# FPGA_Banks.net
KiCad netlist of a schematic drawn in Altium Designer
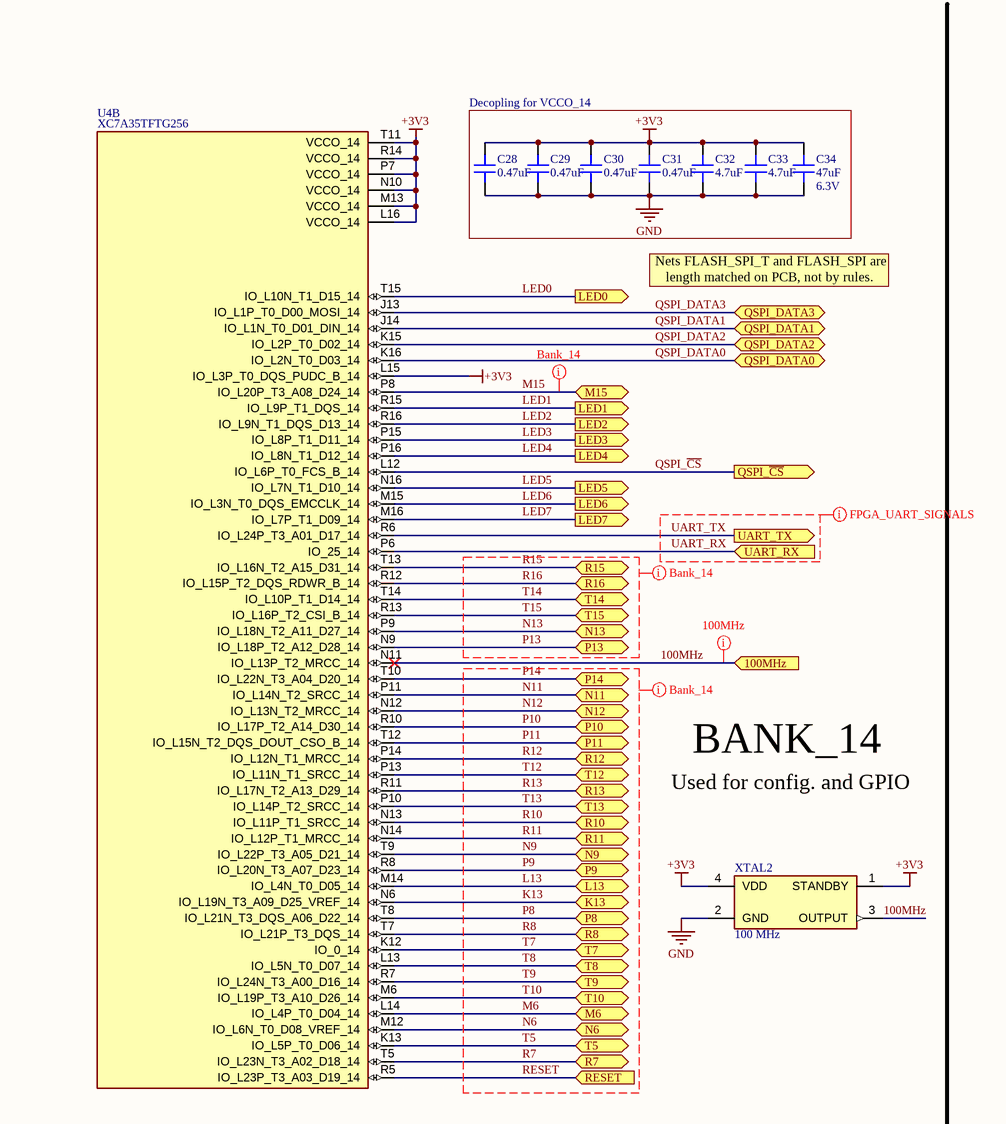
[diagram p0: FPGA_Banks.SchDoc, top left]
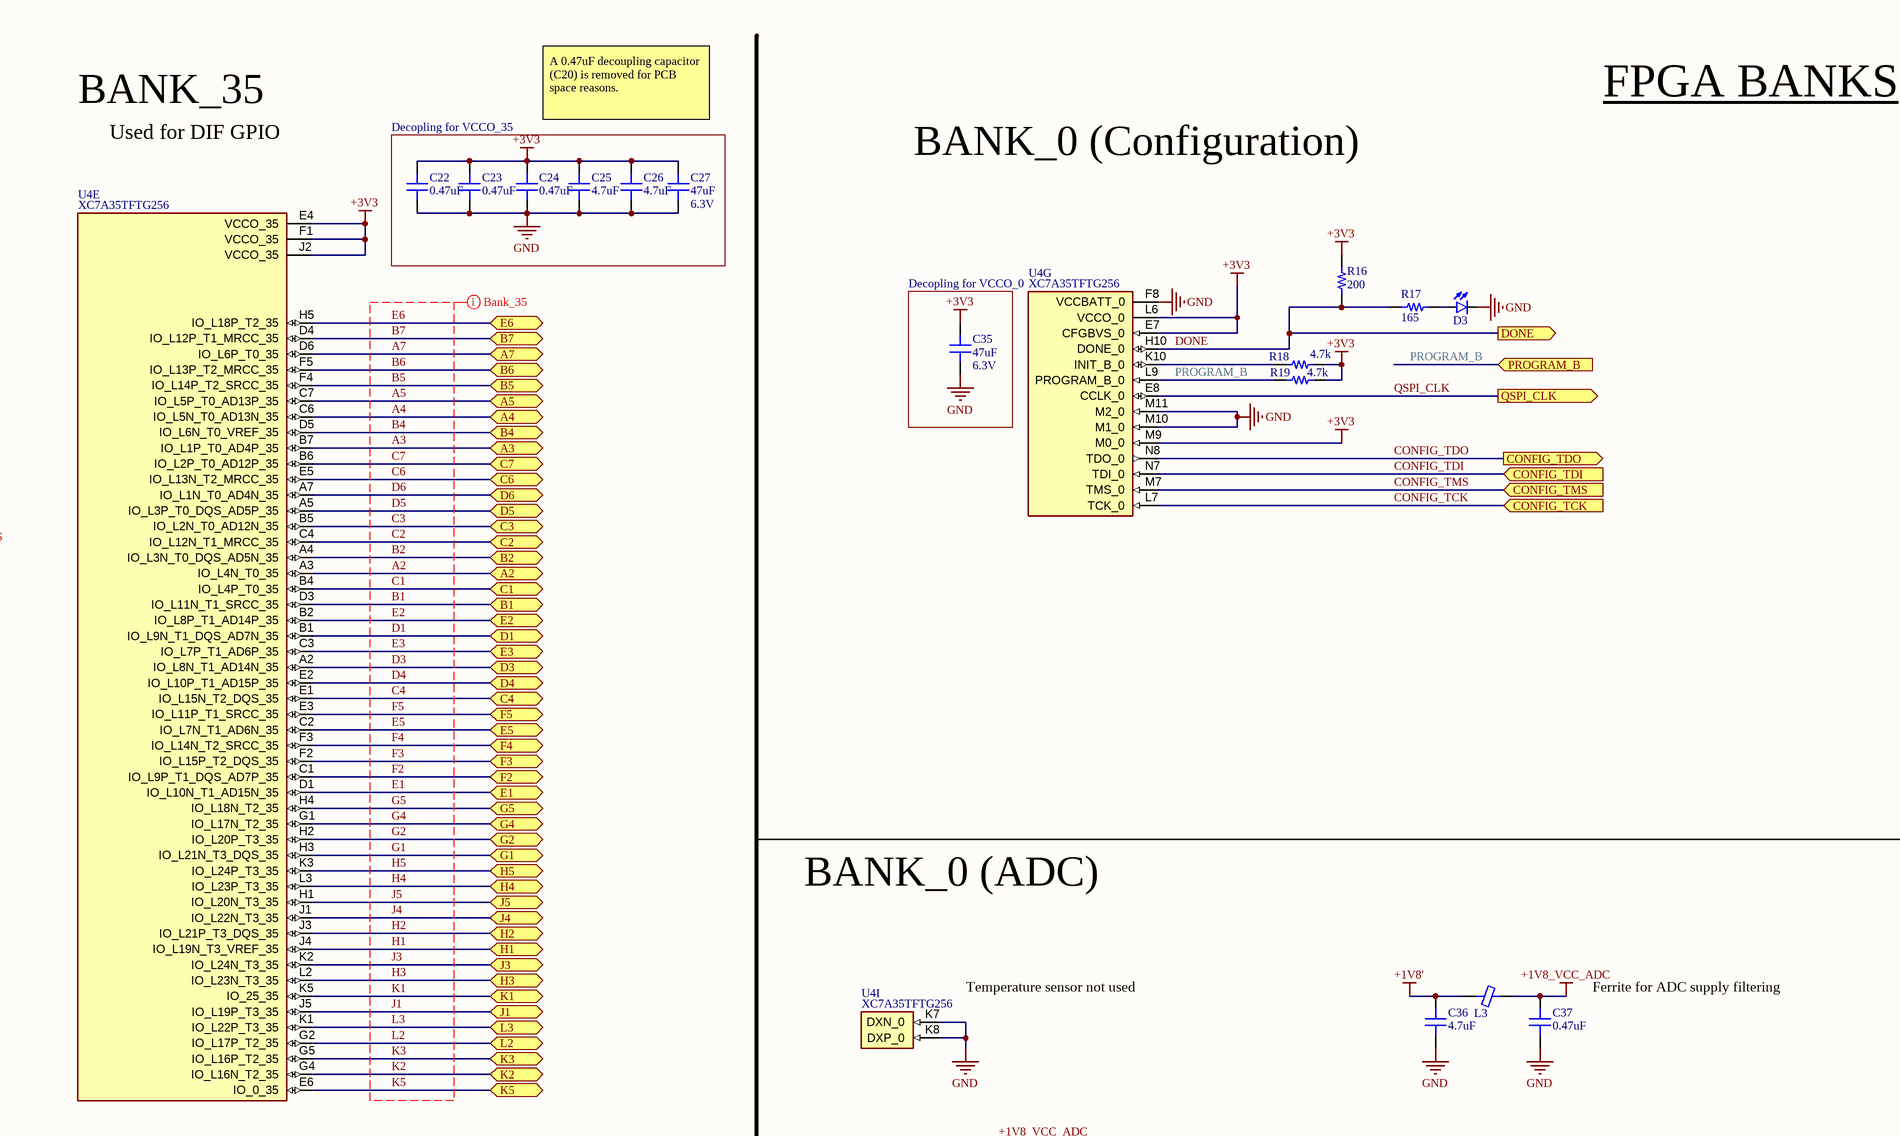
[diagram p1: FPGA_Banks.SchDoc, top right]
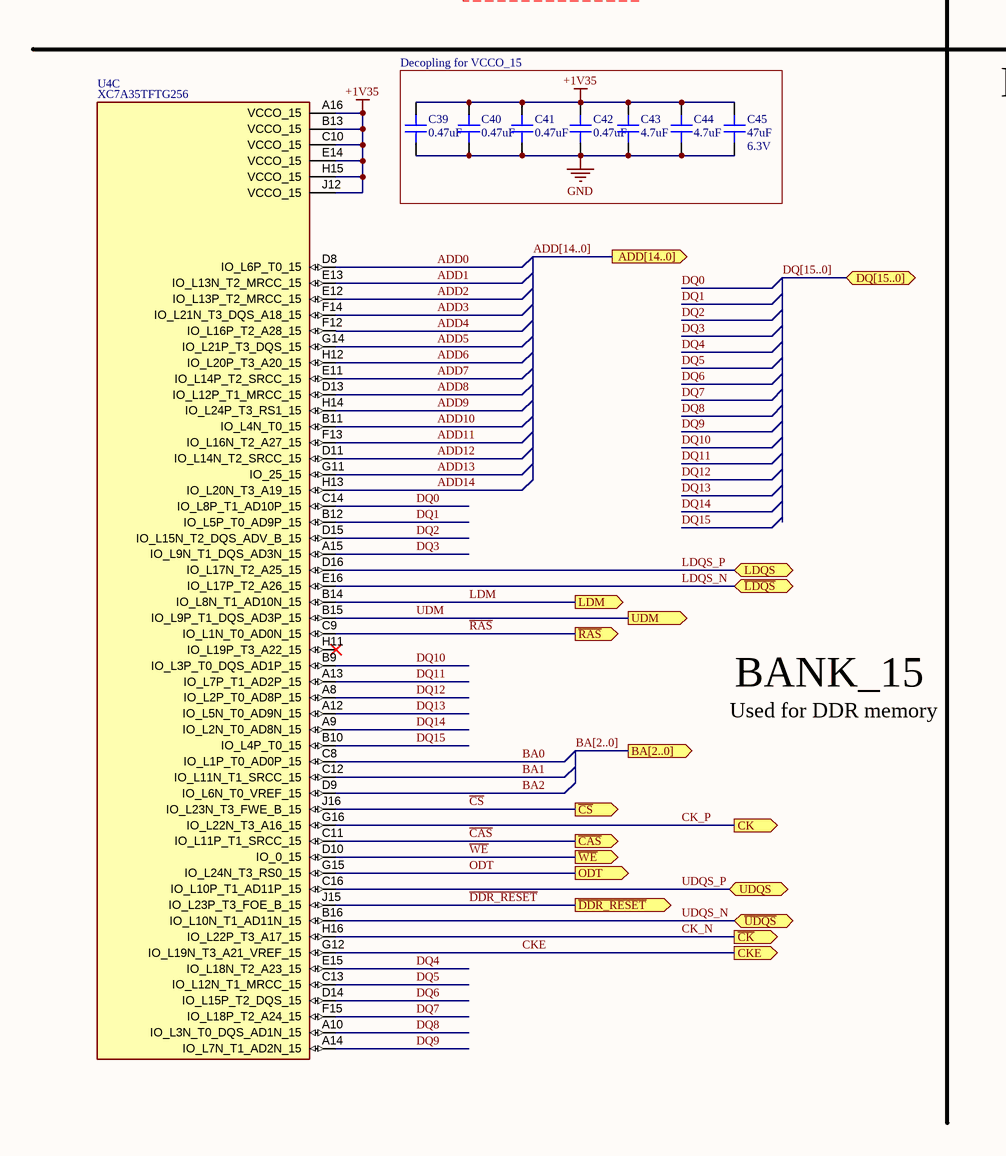
[diagram p2: FPGA_Banks.SchDoc, bottom left]
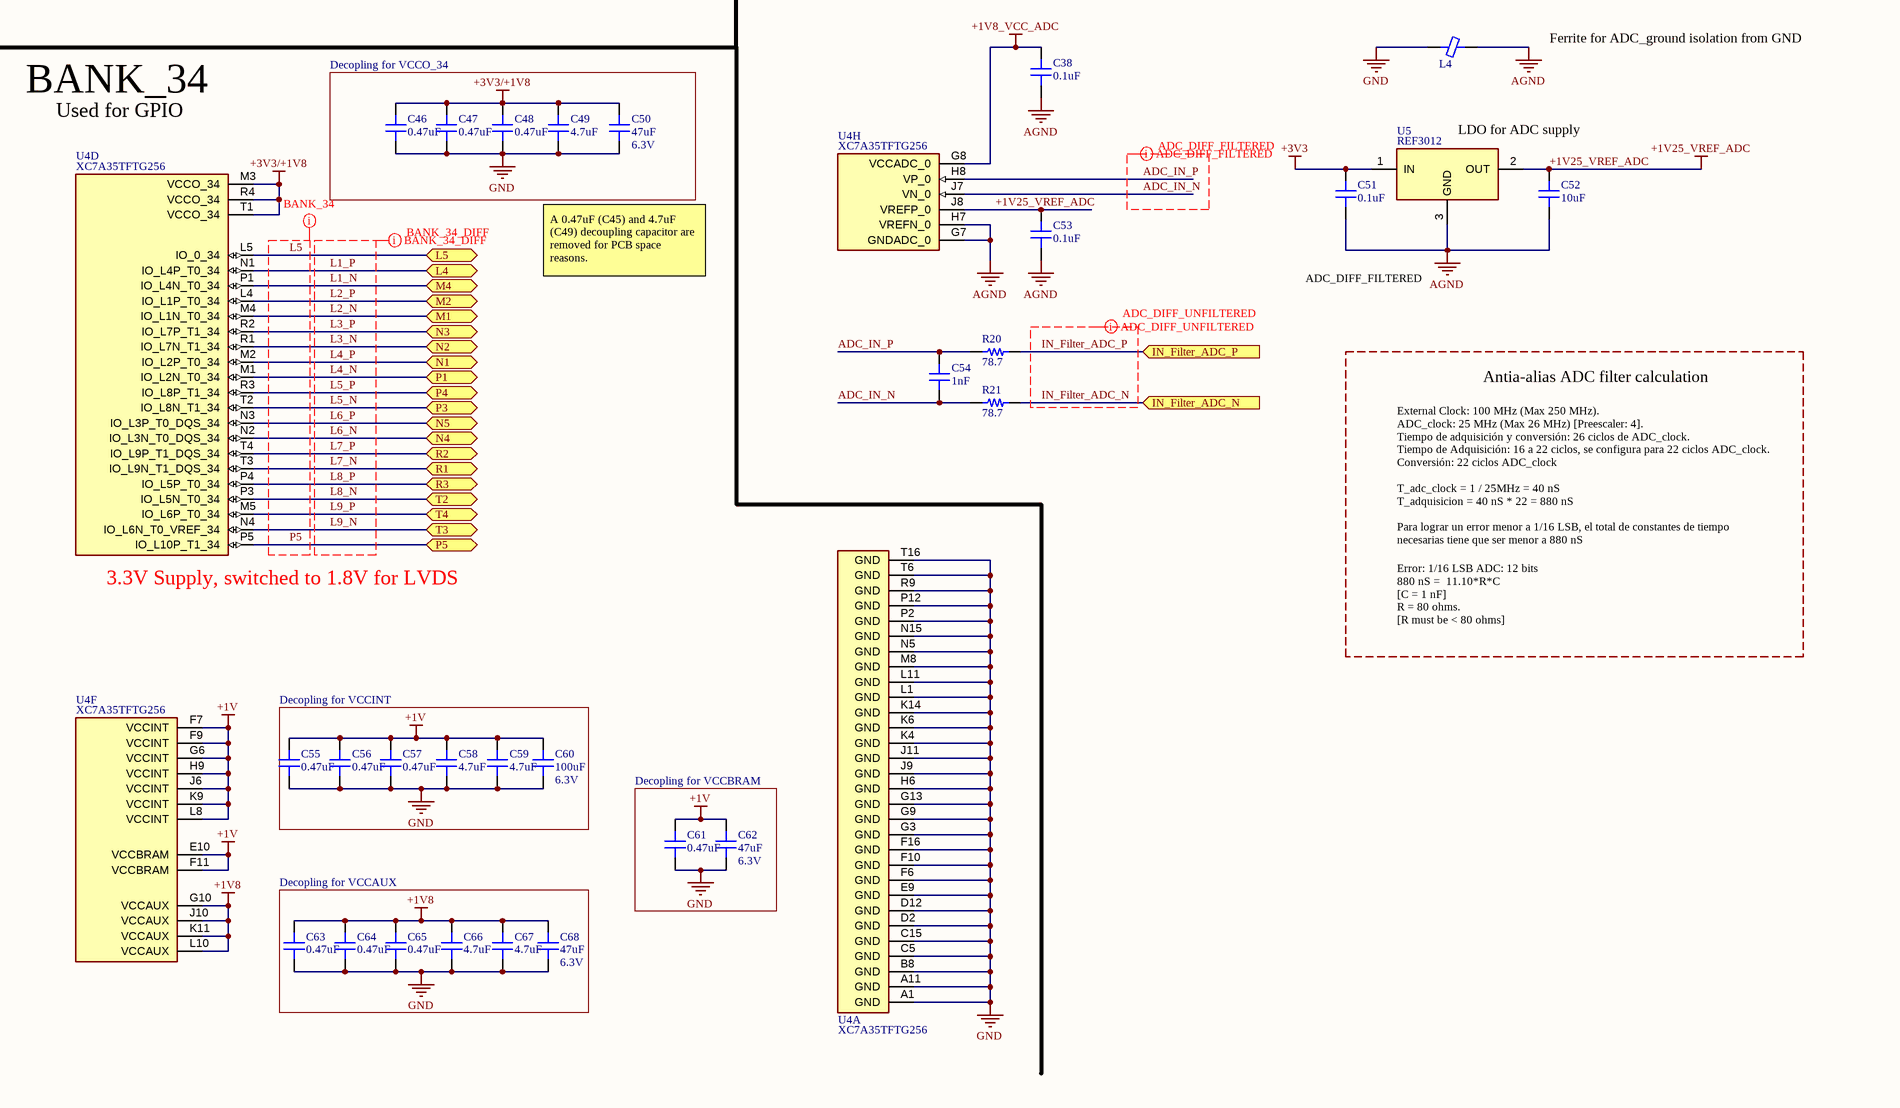
[diagram p3: FPGA_Banks.SchDoc, bottom right]

(export (version "E")
  (design (tool "Eeschema 10.0.6"))
  (components
    (comp (ref "C22")
      (value "0.47uF")
      (footprint "CAP0402")
      (description "CAP CER 0.47uF 10V X7R 0402 10%")
      (fields (field (name "PARTNUMBER") "C0603C474K4RAC") (field (name "TOLERANCE") "10%"))
      (libsource (lib "Pasivos") (part "C0402C474K8RAC"))
    )
    (comp (ref "C23")
      (value "0.47uF")
      (footprint "CAP0402")
      (description "CAP CER 0.47uF 10V X7R 0402 10%")
      (fields (field (name "PARTNUMBER") "C0603C474K4RAC") (field (name "TOLERANCE") "10%"))
      (libsource (lib "Pasivos") (part "C0402C474K8RAC"))
    )
    (comp (ref "C24")
      (value "0.47uF")
      (footprint "CAP0402")
      (description "CAP CER 0.47uF 10V X7R 0402 10%")
      (fields (field (name "PARTNUMBER") "C0603C474K4RAC") (field (name "TOLERANCE") "10%"))
      (libsource (lib "Pasivos") (part "C0402C474K8RAC"))
    )
    (comp (ref "C25")
      (value "4.7uF")
      (footprint "CAP0402")
      (description "CAP CER 4.7uF 6.3V X5R 0402 10%")
      (fields (field (name "PARTNUMBER") "C0402C475M9PAC") (field (name "TOLERANCE") "10%"))
      (libsource (lib "Pasivos") (part "C0402C475M9PAC"))
    )
    (comp (ref "C26")
      (value "4.7uF")
      (footprint "CAP0402")
      (description "CAP CER 4.7uF 6.3V X5R 0402 10%")
      (fields (field (name "PARTNUMBER") "C0402C475M9PAC") (field (name "TOLERANCE") "10%"))
      (libsource (lib "Pasivos") (part "C0402C475M9PAC"))
    )
    (comp (ref "C27")
      (value "47uF")
      (footprint "CAP0805")
      (description "CAP CER 47uF 6.3V X5R 0805 20%")
      (fields
        (field (name "VOLTAGE") "6.3V")
        (field (name "MANUFACTURER") "Samsung")
        (field (name "TOLERANCE") "20%")
      )
      (libsource (lib "Pasivos") (part "CL21A476MQYNNNE"))
    )
    (comp (ref "C28")
      (value "0.47uF")
      (footprint "CAP0402")
      (description "CAP CER 0.47uF 10V X7R 0402 10%")
      (fields (field (name "PARTNUMBER") "C0603C474K4RAC") (field (name "TOLERANCE") "10%"))
      (libsource (lib "Pasivos") (part "C0402C474K8RAC"))
    )
    (comp (ref "C29")
      (value "0.47uF")
      (footprint "CAP0402")
      (description "CAP CER 0.47uF 10V X7R 0402 10%")
      (fields (field (name "PARTNUMBER") "C0603C474K4RAC") (field (name "TOLERANCE") "10%"))
      (libsource (lib "Pasivos") (part "C0402C474K8RAC"))
    )
    (comp (ref "C30")
      (value "0.47uF")
      (footprint "CAP0402")
      (description "CAP CER 0.47uF 10V X7R 0402 10%")
      (fields (field (name "PARTNUMBER") "C0603C474K4RAC") (field (name "TOLERANCE") "10%"))
      (libsource (lib "Pasivos") (part "C0402C474K8RAC"))
    )
    (comp (ref "C31")
      (value "0.47uF")
      (footprint "CAP0402")
      (description "CAP CER 0.47uF 10V X7R 0402 10%")
      (fields (field (name "PARTNUMBER") "C0603C474K4RAC") (field (name "TOLERANCE") "10%"))
      (libsource (lib "Pasivos") (part "C0402C474K8RAC"))
    )
    (comp (ref "C32")
      (value "4.7uF")
      (footprint "CAP0402")
      (description "CAP CER 4.7uF 6.3V X5R 0402 10%")
      (fields (field (name "PARTNUMBER") "C0402C475M9PAC") (field (name "TOLERANCE") "10%"))
      (libsource (lib "Pasivos") (part "C0402C475M9PAC"))
    )
    (comp (ref "C33")
      (value "4.7uF")
      (footprint "CAP0402")
      (description "CAP CER 4.7uF 6.3V X5R 0402 10%")
      (fields (field (name "PARTNUMBER") "C0402C475M9PAC") (field (name "TOLERANCE") "10%"))
      (libsource (lib "Pasivos") (part "C0402C475M9PAC"))
    )
    (comp (ref "C34")
      (value "47uF")
      (footprint "CAP0805")
      (description "CAP CER 47uF 6.3V X5R 0805 20%")
      (fields
        (field (name "VOLTAGE") "6.3V")
        (field (name "MANUFACTURER") "Samsung")
        (field (name "TOLERANCE") "20%")
      )
      (libsource (lib "Pasivos") (part "CL21A476MQYNNNE"))
    )
    (comp (ref "C35")
      (value "47uF")
      (footprint "CAP0805")
      (description "CAP CER 47uF 6.3V X5R 0805 20%")
      (fields
        (field (name "MANUFACTURER") "Samsung")
        (field (name "VOLTAGE") "6.3V")
        (field (name "TOLERANCE") "20%")
      )
      (libsource (lib "Pasivos") (part "CL21A476MQYNNNE"))
    )
    (comp (ref "C36")
      (value "4.7uF")
      (footprint "CAP0402")
      (description "CAP CER 4.7uF 6.3V X5R 0402 10%")
      (fields (field (name "PARTNUMBER") "C0402C475M9PAC") (field (name "TOLERANCE") "10%"))
      (libsource (lib "Pasivos") (part "C0402C475M9PAC"))
    )
    (comp (ref "C37")
      (value "0.47uF")
      (footprint "CAP0402")
      (description "CAP CER 0.47uF 10V X7R 0402 10%")
      (fields (field (name "PARTNUMBER") "C0603C474K4RAC") (field (name "TOLERANCE") "10%"))
      (libsource (lib "Pasivos") (part "C0402C474K8RAC"))
    )
    (comp (ref "C38")
      (value "0.1uF")
      (footprint "CAP0402")
      (description "CAP CER 0.1uF 16V X7R 0402 10%")
      (fields (field (name "TOLERANCE") "10%") (field (name "VOLTAGE") "16V"))
      (libsource (lib "Pasivos") (part "C0402C104K4RAC"))
    )
    (comp (ref "C39")
      (value "0.47uF")
      (footprint "CAP0402")
      (description "CAP CER 0.47uF 10V X7R 0402 10%")
      (fields (field (name "PARTNUMBER") "C0603C474K4RAC") (field (name "TOLERANCE") "10%"))
      (libsource (lib "Pasivos") (part "C0402C474K8RAC"))
    )
    (comp (ref "C40")
      (value "0.47uF")
      (footprint "CAP0402")
      (description "CAP CER 0.47uF 10V X7R 0402 10%")
      (fields (field (name "PARTNUMBER") "C0603C474K4RAC") (field (name "TOLERANCE") "10%"))
      (libsource (lib "Pasivos") (part "C0402C474K8RAC"))
    )
    (comp (ref "C41")
      (value "0.47uF")
      (footprint "CAP0402")
      (description "CAP CER 0.47uF 10V X7R 0402 10%")
      (fields (field (name "PARTNUMBER") "C0603C474K4RAC") (field (name "TOLERANCE") "10%"))
      (libsource (lib "Pasivos") (part "C0402C474K8RAC"))
    )
    (comp (ref "C42")
      (value "0.47uF")
      (footprint "CAP0402")
      (description "CAP CER 0.47uF 10V X7R 0402 10%")
      (fields (field (name "PARTNUMBER") "C0603C474K4RAC") (field (name "TOLERANCE") "10%"))
      (libsource (lib "Pasivos") (part "C0402C474K8RAC"))
    )
    (comp (ref "C43")
      (value "4.7uF")
      (footprint "CAP0402")
      (description "CAP CER 4.7uF 6.3V X5R 0402 10%")
      (fields (field (name "PARTNUMBER") "C0402C475M9PAC") (field (name "TOLERANCE") "10%"))
      (libsource (lib "Pasivos") (part "C0402C475M9PAC"))
    )
    (comp (ref "C44")
      (value "4.7uF")
      (footprint "CAP0402")
      (description "CAP CER 4.7uF 6.3V X5R 0402 10%")
      (fields (field (name "PARTNUMBER") "C0402C475M9PAC") (field (name "TOLERANCE") "10%"))
      (libsource (lib "Pasivos") (part "C0402C475M9PAC"))
    )
    (comp (ref "C45")
      (value "47uF")
      (footprint "CAP0805")
      (description "CAP CER 47uF 6.3V X5R 0805 20%")
      (fields
        (field (name "VOLTAGE") "6.3V")
        (field (name "MANUFACTURER") "Samsung")
        (field (name "TOLERANCE") "20%")
      )
      (libsource (lib "Pasivos") (part "CL21A476MQYNNNE"))
    )
    (comp (ref "C46")
      (value "0.47uF")
      (footprint "CAP0402")
      (description "CAP CER 0.47uF 10V X7R 0402 10%")
      (fields (field (name "PARTNUMBER") "C0603C474K4RAC") (field (name "TOLERANCE") "10%"))
      (libsource (lib "Pasivos") (part "C0402C474K8RAC"))
    )
    (comp (ref "C47")
      (value "0.47uF")
      (footprint "CAP0402")
      (description "CAP CER 0.47uF 10V X7R 0402 10%")
      (fields (field (name "PARTNUMBER") "C0603C474K4RAC") (field (name "TOLERANCE") "10%"))
      (libsource (lib "Pasivos") (part "C0402C474K8RAC"))
    )
    (comp (ref "C48")
      (value "0.47uF")
      (footprint "CAP0402")
      (description "CAP CER 0.47uF 10V X7R 0402 10%")
      (fields (field (name "PARTNUMBER") "C0603C474K4RAC") (field (name "TOLERANCE") "10%"))
      (libsource (lib "Pasivos") (part "C0402C474K8RAC"))
    )
    (comp (ref "C49")
      (value "4.7uF")
      (footprint "CAP0402")
      (description "CAP CER 4.7uF 6.3V X5R 0402 10%")
      (fields (field (name "PARTNUMBER") "C0402C475M9PAC") (field (name "TOLERANCE") "10%"))
      (libsource (lib "Pasivos") (part "C0402C475M9PAC"))
    )
    (comp (ref "C50")
      (value "47uF")
      (footprint "CAP0805")
      (description "CAP CER 47uF 6.3V X5R 0805 20%")
      (fields
        (field (name "VOLTAGE") "6.3V")
        (field (name "MANUFACTURER") "Samsung")
        (field (name "TOLERANCE") "20%")
      )
      (libsource (lib "Pasivos") (part "CL21A476MQYNNNE"))
    )
    (comp (ref "C51")
      (value "0.1uF")
      (footprint "CAP0402")
      (description "CAP CER 0.1uF 16V X7R 0402 10%")
      (fields (field (name "TOLERANCE") "10%") (field (name "VOLTAGE") "16V"))
      (libsource (lib "Pasivos") (part "C0402C104K4RAC"))
    )
    (comp (ref "C52")
      (value "10uF")
      (footprint "CAP0402")
      (description "CAP CER 10uF 6.3V X5R 0402 10%")
      (fields (field (name "TOLERANCE") "10%") (field (name "MANUFACTURER") "Kemet"))
      (libsource (lib "Pasivos") (part "C0402C106M9PAC"))
    )
    (comp (ref "C53")
      (value "0.1uF")
      (footprint "CAP0402")
      (description "CAP CER 0.1uF 16V X7R 0402 10%")
      (fields (field (name "TOLERANCE") "10%") (field (name "VOLTAGE") "16V"))
      (libsource (lib "Pasivos") (part "C0402C104K4RAC"))
    )
    (comp (ref "C54")
      (value "1nF")
      (footprint "CAP0402")
      (description "CAP CER 1nF 16V X7R 0402 10%")
      (fields (field (name "TOLERANCE") "10%") (field (name "PARTNUMBER") "C0402C102K4RAC"))
      (libsource (lib "Pasivos") (part "C0402C102K4RAC"))
    )
    (comp (ref "C55")
      (value "0.47uF")
      (footprint "CAP0402")
      (description "CAP CER 0.47uF 10V X7R 0402 10%")
      (fields (field (name "PARTNUMBER") "C0603C474K4RAC") (field (name "TOLERANCE") "10%"))
      (libsource (lib "Pasivos") (part "C0402C474K8RAC"))
    )
    (comp (ref "C56")
      (value "0.47uF")
      (footprint "CAP0402")
      (description "CAP CER 0.47uF 10V X7R 0402 10%")
      (fields (field (name "PARTNUMBER") "C0603C474K4RAC") (field (name "TOLERANCE") "10%"))
      (libsource (lib "Pasivos") (part "C0402C474K8RAC"))
    )
    (comp (ref "C57")
      (value "0.47uF")
      (footprint "CAP0402")
      (description "CAP CER 0.47uF 10V X7R 0402 10%")
      (fields (field (name "PARTNUMBER") "C0603C474K4RAC") (field (name "TOLERANCE") "10%"))
      (libsource (lib "Pasivos") (part "C0402C474K8RAC"))
    )
    (comp (ref "C58")
      (value "4.7uF")
      (footprint "CAP0402")
      (description "CAP CER 4.7uF 6.3V X5R 0402 10%")
      (fields (field (name "PARTNUMBER") "C0402C475M9PAC") (field (name "TOLERANCE") "10%"))
      (libsource (lib "Pasivos") (part "C0402C475M9PAC"))
    )
    (comp (ref "C59")
      (value "4.7uF")
      (footprint "CAP0402")
      (description "CAP CER 4.7uF 6.3V X5R 0402 10%")
      (fields (field (name "PARTNUMBER") "C0402C475M9PAC") (field (name "TOLERANCE") "10%"))
      (libsource (lib "Pasivos") (part "C0402C475M9PAC"))
    )
    (comp (ref "C60")
      (value "100uF")
      (footprint "CAP1206")
      (description "CAP CER 100uF 6.3V X5R 1206 20%")
      (fields
        (field (name "PARTNUMBER") "C1206C107M9PAC")
        (field (name "TOLERANCE") "20%")
        (field (name "VOLTAGE") "6.3V")
      )
      (libsource (lib "Pasivos") (part "C1206C107M9PAC"))
    )
    (comp (ref "C61")
      (value "0.47uF")
      (footprint "CAP0402")
      (description "CAP CER 0.47uF 10V X7R 0402 10%")
      (fields (field (name "PARTNUMBER") "C0603C474K4RAC") (field (name "TOLERANCE") "10%"))
      (libsource (lib "Pasivos") (part "C0402C474K8RAC"))
    )
    (comp (ref "C62")
      (value "47uF")
      (footprint "CAP0805")
      (description "CAP CER 47uF 6.3V X5R 0805 20%")
      (fields
        (field (name "VOLTAGE") "6.3V")
        (field (name "MANUFACTURER") "Samsung")
        (field (name "TOLERANCE") "20%")
      )
      (libsource (lib "Pasivos") (part "CL21A476MQYNNNE"))
    )
    (comp (ref "C63")
      (value "0.47uF")
      (footprint "CAP0402")
      (description "CAP CER 0.47uF 10V X7R 0402 10%")
      (fields (field (name "PARTNUMBER") "C0603C474K4RAC") (field (name "TOLERANCE") "10%"))
      (libsource (lib "Pasivos") (part "C0402C474K8RAC"))
    )
    (comp (ref "C64")
      (value "0.47uF")
      (footprint "CAP0402")
      (description "CAP CER 0.47uF 10V X7R 0402 10%")
      (fields (field (name "PARTNUMBER") "C0603C474K4RAC") (field (name "TOLERANCE") "10%"))
      (libsource (lib "Pasivos") (part "C0402C474K8RAC"))
    )
    (comp (ref "C65")
      (value "0.47uF")
      (footprint "CAP0402")
      (description "CAP CER 0.47uF 10V X7R 0402 10%")
      (fields (field (name "PARTNUMBER") "C0603C474K4RAC") (field (name "TOLERANCE") "10%"))
      (libsource (lib "Pasivos") (part "C0402C474K8RAC"))
    )
    (comp (ref "C66")
      (value "4.7uF")
      (footprint "CAP0402")
      (description "CAP CER 4.7uF 6.3V X5R 0402 10%")
      (fields (field (name "PARTNUMBER") "C0402C475M9PAC") (field (name "TOLERANCE") "10%"))
      (libsource (lib "Pasivos") (part "C0402C475M9PAC"))
    )
    (comp (ref "C67")
      (value "4.7uF")
      (footprint "CAP0402")
      (description "CAP CER 4.7uF 6.3V X5R 0402 10%")
      (fields (field (name "PARTNUMBER") "C0402C475M9PAC") (field (name "TOLERANCE") "10%"))
      (libsource (lib "Pasivos") (part "C0402C475M9PAC"))
    )
    (comp (ref "C68")
      (value "47uF")
      (footprint "CAP0805")
      (description "CAP CER 47uF 6.3V X5R 0805 20%")
      (fields
        (field (name "VOLTAGE") "6.3V")
        (field (name "MANUFACTURER") "Samsung")
        (field (name "TOLERANCE") "20%")
      )
      (libsource (lib "Pasivos") (part "CL21A476MQYNNNE"))
    )
    (comp (ref "D3")
      (value "597-3305-607F")
      (footprint "0603_LED")
      (description "LED blue diffused 0603 SMD")
      (fields (field (name "MANUFACTURER") "Würth Elektronik") (field (name "PARTNUMBER") "150060BS55040"))
      (libsource (lib "Integrated_Circuits") (part "LED_BLUE_0603"))
    )
    (comp (ref "L3")
      (value "HZ0603C651R-10")
      (footprint "Fer0603")
      (description "FERRITE BEAD, 650 OHM, 0603, 1LN, 0603")
      (fields (field (name "MANUFACTURER") "Laird-Signal Integrity Products"))
      (libsource (lib "Pasivos") (part "HZ0603C651R-10"))
    )
    (comp (ref "L4")
      (value "HZ0603C651R-10")
      (footprint "Fer0603")
      (description "FERRITE BEAD, 650 OHM, 0603, 1LN, 0603")
      (fields (field (name "MANUFACTURER") "Laird-Signal Integrity Products"))
      (libsource (lib "Pasivos") (part "HZ0603C651R-10"))
    )
    (comp (ref "R16")
      (value "200")
      (footprint "RES0402")
      (description "RES SMD 200 OHM 1% 0.063W 0402")
      (fields (field (name "POWER") "0.063W") (field (name "MANUFACTURER") "Vishay"))
      (libsource (lib "Pasivos") (part "CRCW0402200RFK"))
    )
    (comp (ref "R17")
      (value "165")
      (footprint "RES0402")
      (description "RES SMD 165 OHM 1% 0.063W 0402")
      (fields (field (name "MANUFACTURER") "Vishay") (field (name "TOLERANCE") "1%"))
      (libsource (lib "Pasivos") (part "CRCW0402165RFK"))
    )
    (comp (ref "R18")
      (value "4.7k")
      (footprint "RES0402")
      (description "RES SMD 4.7K OHM 1% 0.063W 0402")
      (fields (field (name "POWER") "0.063 W") (field (name "MANUFACTURER") "Vishay"))
      (libsource (lib "Pasivos") (part "CRCW04024K70FK"))
    )
    (comp (ref "R19")
      (value "4.7k")
      (footprint "RES0402")
      (description "RES SMD 4.7K OHM 1% 0.063W 0402")
      (fields (field (name "POWER") "0.063 W") (field (name "MANUFACTURER") "Vishay"))
      (libsource (lib "Pasivos") (part "CRCW04024K70FK"))
    )
    (comp (ref "R20")
      (value "78.7")
      (footprint "RES0402")
      (description "RES SMD 78.7 OHM 1% 0.063W 0402")
      (fields (field (name "MANUFACTURER") "Vishay") (field (name "TOLERANCE") "1%"))
      (libsource (lib "Pasivos") (part "CRCW040278R7FK"))
    )
    (comp (ref "R21")
      (value "78.7")
      (footprint "RES0402")
      (description "RES SMD 78.7 OHM 1% 0.063W 0402")
      (fields (field (name "MANUFACTURER") "Vishay") (field (name "TOLERANCE") "1%"))
      (libsource (lib "Pasivos") (part "CRCW040278R7FK"))
    )
    (comp (ref "U4")
      (value "XC7A35TFTG256")
      (footprint "BGA-256")
      (description "FPGA - 170 I/O 256FTBGA")
      (fields (field (name "MANUFACTURER") "AMD - Xilinx") (field (name "PARTNUMBER") "XC7A35T-xFTG256"))
      (libsource (lib "") (part "XC7A35TFTG256_4"))
    )
    (comp (ref "U5")
      (value "REF3012")
      (footprint "SOT23-3")
      (description "Voltage Reference 1.5V")
      (fields (field (name "MANUFACTURER") "Texas Instruments") (field (name "PARTNUMBER") "REF3012AIDBZR"))
      (libsource (lib "Integrated_Circuits") (part "REF3012"))
    )
    (comp (ref "XTAL2")
      (value "ASFLMB-100.000MHZ-LC-T")
      (footprint "XTAL_ASFLMB")
      (description "Crystal 100 MHz")
      (fields (field (name "MANUFACTURER") "Abracom") (field (name "FREQUENCY") "100 MHz"))
      (libsource (lib "Integrated_Circuits") (part "XTAL_100MHz"))
    )
  )
  (nets
    (net (code "1") (name "+1V") (class "Default")
      (node (ref "C55") (pin "2") (pinfunction "2_2") (pintype "passive"))
      (node (ref "C56") (pin "2") (pinfunction "2_2") (pintype "passive"))
      (node (ref "C57") (pin "2") (pinfunction "2_2") (pintype "passive"))
      (node (ref "C58") (pin "2") (pinfunction "2_2") (pintype "passive"))
      (node (ref "C59") (pin "2") (pinfunction "2_2") (pintype "passive"))
      (node (ref "C60") (pin "2") (pinfunction "2_2") (pintype "passive"))
      (node (ref "C61") (pin "2") (pinfunction "2_2") (pintype "passive"))
      (node (ref "C62") (pin "2") (pinfunction "2_2") (pintype "passive"))
      (node (ref "U4") (pin "E10") (pinfunction "VCCBRAM_E10") (pintype "power_in"))
      (node (ref "U4") (pin "F11") (pinfunction "VCCBRAM_F11") (pintype "power_in"))
      (node (ref "U4") (pin "F7") (pinfunction "VCCINT_F7") (pintype "power_in"))
      (node (ref "U4") (pin "F9") (pinfunction "VCCINT_F9") (pintype "power_in"))
      (node (ref "U4") (pin "G6") (pinfunction "VCCINT_G6") (pintype "power_in"))
      (node (ref "U4") (pin "H9") (pinfunction "VCCINT_H9") (pintype "power_in"))
      (node (ref "U4") (pin "J6") (pinfunction "VCCINT_J6") (pintype "power_in"))
      (node (ref "U4") (pin "K9") (pinfunction "VCCINT_K9") (pintype "power_in"))
      (node (ref "U4") (pin "L8") (pinfunction "VCCINT_L8") (pintype "power_in"))
    )
    (net (code "2") (name "+1V8") (class "Default")
      (node (ref "C63") (pin "2") (pinfunction "2_2") (pintype "passive"))
      (node (ref "C64") (pin "2") (pinfunction "2_2") (pintype "passive"))
      (node (ref "C65") (pin "2") (pinfunction "2_2") (pintype "passive"))
      (node (ref "C66") (pin "2") (pinfunction "2_2") (pintype "passive"))
      (node (ref "C67") (pin "2") (pinfunction "2_2") (pintype "passive"))
      (node (ref "C68") (pin "2") (pinfunction "2_2") (pintype "passive"))
      (node (ref "U4") (pin "G10") (pinfunction "VCCAUX_G10") (pintype "power_in"))
      (node (ref "U4") (pin "J10") (pinfunction "VCCAUX_J10") (pintype "power_in"))
      (node (ref "U4") (pin "K11") (pinfunction "VCCAUX_K11") (pintype "power_in"))
      (node (ref "U4") (pin "L10") (pinfunction "VCCAUX_L10") (pintype "power_in"))
    )
    (net (code "3") (name "+1V8'") (class "Default")
      (node (ref "C36") (pin "2") (pinfunction "2_2") (pintype "passive"))
      (node (ref "L3") (pin "1") (pinfunction "1_1") (pintype "passive"))
    )
    (net (code "4") (name "+1V8_VCC_ADC") (class "Default")
      (node (ref "C37") (pin "2") (pinfunction "2_2") (pintype "passive"))
      (node (ref "C38") (pin "2") (pinfunction "2_2") (pintype "passive"))
      (node (ref "L3") (pin "2") (pinfunction "2_2") (pintype "passive"))
      (node (ref "U4") (pin "G8") (pinfunction "VCCADC_0_G8") (pintype "power_in"))
    )
    (net (code "5") (name "+1V25_VREF_ADC") (class "Default")
      (node (ref "C52") (pin "2") (pinfunction "2_2") (pintype "passive"))
      (node (ref "C53") (pin "2") (pinfunction "2_2") (pintype "passive"))
      (node (ref "U4") (pin "J8") (pinfunction "VREFP_0_J8") (pintype "power_in"))
      (node (ref "U5") (pin "2") (pinfunction "OUT_2") (pintype "power_in"))
    )
    (net (code "6") (name "+1V35") (class "Default")
      (node (ref "C39") (pin "2") (pinfunction "2_2") (pintype "passive"))
      (node (ref "C40") (pin "2") (pinfunction "2_2") (pintype "passive"))
      (node (ref "C41") (pin "2") (pinfunction "2_2") (pintype "passive"))
      (node (ref "C42") (pin "2") (pinfunction "2_2") (pintype "passive"))
      (node (ref "C43") (pin "2") (pinfunction "2_2") (pintype "passive"))
      (node (ref "C44") (pin "2") (pinfunction "2_2") (pintype "passive"))
      (node (ref "C45") (pin "2") (pinfunction "2_2") (pintype "passive"))
      (node (ref "U4") (pin "A16") (pinfunction "VCCO_15_A16") (pintype "power_in"))
      (node (ref "U4") (pin "B13") (pinfunction "VCCO_15_B13") (pintype "power_in"))
      (node (ref "U4") (pin "C10") (pinfunction "VCCO_15_C10") (pintype "power_in"))
      (node (ref "U4") (pin "E14") (pinfunction "VCCO_15_E14") (pintype "power_in"))
      (node (ref "U4") (pin "H15") (pinfunction "VCCO_15_H15") (pintype "power_in"))
      (node (ref "U4") (pin "J12") (pinfunction "VCCO_15_J12") (pintype "power_in"))
    )
    (net (code "7") (name "+3V3") (class "Default")
      (node (ref "C22") (pin "2") (pinfunction "2_2") (pintype "passive"))
      (node (ref "C23") (pin "2") (pinfunction "2_2") (pintype "passive"))
      (node (ref "C24") (pin "2") (pinfunction "2_2") (pintype "passive"))
      (node (ref "C25") (pin "2") (pinfunction "2_2") (pintype "passive"))
      (node (ref "C26") (pin "2") (pinfunction "2_2") (pintype "passive"))
      (node (ref "C27") (pin "2") (pinfunction "2_2") (pintype "passive"))
      (node (ref "C28") (pin "2") (pinfunction "2_2") (pintype "passive"))
      (node (ref "C29") (pin "2") (pinfunction "2_2") (pintype "passive"))
      (node (ref "C30") (pin "2") (pinfunction "2_2") (pintype "passive"))
      (node (ref "C31") (pin "2") (pinfunction "2_2") (pintype "passive"))
      (node (ref "C32") (pin "2") (pinfunction "2_2") (pintype "passive"))
      (node (ref "C33") (pin "2") (pinfunction "2_2") (pintype "passive"))
      (node (ref "C34") (pin "2") (pinfunction "2_2") (pintype "passive"))
      (node (ref "C35") (pin "2") (pinfunction "2_2") (pintype "passive"))
      (node (ref "C51") (pin "2") (pinfunction "2_2") (pintype "passive"))
      (node (ref "R16") (pin "2") (pinfunction "2_2") (pintype "passive"))
      (node (ref "R18") (pin "2") (pinfunction "2_2") (pintype "passive"))
      (node (ref "R19") (pin "2") (pinfunction "2_2") (pintype "passive"))
      (node (ref "U4") (pin "E4") (pinfunction "VCCO_35_E4") (pintype "power_in"))
      (node (ref "U4") (pin "E7") (pinfunction "CFGBVS_0_E7") (pintype "input"))
      (node (ref "U4") (pin "F1") (pinfunction "VCCO_35_F1") (pintype "power_in"))
      (node (ref "U4") (pin "J2") (pinfunction "VCCO_35_J2") (pintype "power_in"))
      (node (ref "U4") (pin "L15") (pinfunction "IO_L3P_T0_DQS_PUDC_B_14_L15") (pintype "bidirectional"))
      (node (ref "U4") (pin "L16") (pinfunction "VCCO_14_L16") (pintype "power_in"))
      (node (ref "U4") (pin "L6") (pinfunction "VCCO_0_L6") (pintype "power_in"))
      (node (ref "U4") (pin "M13") (pinfunction "VCCO_14_M13") (pintype "power_in"))
      (node (ref "U4") (pin "M9") (pinfunction "M0_0_M9") (pintype "input"))
      (node (ref "U4") (pin "N10") (pinfunction "VCCO_14_N10") (pintype "power_in"))
      (node (ref "U4") (pin "P7") (pinfunction "VCCO_14_P7") (pintype "power_in"))
      (node (ref "U4") (pin "R14") (pinfunction "VCCO_14_R14") (pintype "power_in"))
      (node (ref "U4") (pin "T11") (pinfunction "VCCO_14_T11") (pintype "power_in"))
      (node (ref "U5") (pin "1") (pinfunction "IN_1") (pintype "power_in"))
      (node (ref "XTAL2") (pin "1") (pinfunction "STANDBY_1") (pintype "passive"))
      (node (ref "XTAL2") (pin "4") (pinfunction "VDD_4") (pintype "power_in"))
    )
    (net (code "8") (name "+3V3{slash}+1V8") (class "Default")
      (node (ref "C46") (pin "2") (pinfunction "2_2") (pintype "passive"))
      (node (ref "C47") (pin "2") (pinfunction "2_2") (pintype "passive"))
      (node (ref "C48") (pin "2") (pinfunction "2_2") (pintype "passive"))
      (node (ref "C49") (pin "2") (pinfunction "2_2") (pintype "passive"))
      (node (ref "C50") (pin "2") (pinfunction "2_2") (pintype "passive"))
      (node (ref "U4") (pin "M3") (pinfunction "VCCO_34_M3") (pintype "power_in"))
      (node (ref "U4") (pin "R4") (pinfunction "VCCO_34_R4") (pintype "power_in"))
      (node (ref "U4") (pin "T1") (pinfunction "VCCO_34_T1") (pintype "power_in"))
    )
    (net (code "9") (name "/100MHz") (class "Default")
      (node (ref "U4") (pin "N11") (pinfunction "IO_L13P_T2_MRCC_14_N11") (pintype "bidirectional"))
      (node (ref "XTAL2") (pin "3") (pinfunction "OUTPUT_3") (pintype "output"))
    )
    (net (code "10") (name "/A2") (class "Default")
      (node (ref "U4") (pin "A3") (pinfunction "IO_L4N_T0_35_A3") (pintype "bidirectional"))
    )
    (net (code "11") (name "/A3") (class "Default")
      (node (ref "U4") (pin "B7") (pinfunction "IO_L1P_T0_AD4P_35_B7") (pintype "bidirectional"))
    )
    (net (code "12") (name "/A4") (class "Default")
      (node (ref "U4") (pin "C6") (pinfunction "IO_L5N_T0_AD13N_35_C6") (pintype "bidirectional"))
    )
    (net (code "13") (name "/A5") (class "Default")
      (node (ref "U4") (pin "C7") (pinfunction "IO_L5P_T0_AD13P_35_C7") (pintype "bidirectional"))
    )
    (net (code "14") (name "/A7") (class "Default")
      (node (ref "U4") (pin "D6") (pinfunction "IO_L6P_T0_35_D6") (pintype "bidirectional"))
    )
    (net (code "15") (name "/ADC_IN_N") (class "Default")
      (node (ref "C54") (pin "1") (pinfunction "1_1") (pintype "passive"))
      (node (ref "R21") (pin "1") (pinfunction "1_1") (pintype "passive"))
      (node (ref "U4") (pin "J7") (pinfunction "VN_0_J7") (pintype "input"))
    )
    (net (code "16") (name "/ADC_IN_P") (class "Default")
      (node (ref "C54") (pin "2") (pinfunction "2_2") (pintype "passive"))
      (node (ref "R20") (pin "1") (pinfunction "1_1") (pintype "passive"))
      (node (ref "U4") (pin "H8") (pinfunction "VP_0_H8") (pintype "input"))
    )
    (net (code "17") (name "/ADD0") (class "Default")
      (node (ref "U4") (pin "D8") (pinfunction "IO_L6P_T0_15_D8") (pintype "bidirectional"))
    )
    (net (code "18") (name "/ADD1") (class "Default")
      (node (ref "U4") (pin "E13") (pinfunction "IO_L13N_T2_MRCC_15_E13") (pintype "bidirectional"))
    )
    (net (code "19") (name "/ADD2") (class "Default")
      (node (ref "U4") (pin "E12") (pinfunction "IO_L13P_T2_MRCC_15_E12") (pintype "bidirectional"))
    )
    (net (code "20") (name "/ADD3") (class "Default")
      (node (ref "U4") (pin "F14") (pinfunction "IO_L21N_T3_DQS_A18_15_F14") (pintype "bidirectional"))
    )
    (net (code "21") (name "/ADD4") (class "Default")
      (node (ref "U4") (pin "F12") (pinfunction "IO_L16P_T2_A28_15_F12") (pintype "bidirectional"))
    )
    (net (code "22") (name "/ADD5") (class "Default")
      (node (ref "U4") (pin "G14") (pinfunction "IO_L21P_T3_DQS_15_G14") (pintype "bidirectional"))
    )
    (net (code "23") (name "/ADD6") (class "Default")
      (node (ref "U4") (pin "H12") (pinfunction "IO_L20P_T3_A20_15_H12") (pintype "bidirectional"))
    )
    (net (code "24") (name "/ADD7") (class "Default")
      (node (ref "U4") (pin "E11") (pinfunction "IO_L14P_T2_SRCC_15_E11") (pintype "bidirectional"))
    )
    (net (code "25") (name "/ADD8") (class "Default")
      (node (ref "U4") (pin "D13") (pinfunction "IO_L12P_T1_MRCC_15_D13") (pintype "bidirectional"))
    )
    (net (code "26") (name "/ADD9") (class "Default")
      (node (ref "U4") (pin "H14") (pinfunction "IO_L24P_T3_RS1_15_H14") (pintype "bidirectional"))
    )
    (net (code "27") (name "/ADD10") (class "Default")
      (node (ref "U4") (pin "B11") (pinfunction "IO_L4N_T0_15_B11") (pintype "bidirectional"))
    )
    (net (code "28") (name "/ADD11") (class "Default")
      (node (ref "U4") (pin "F13") (pinfunction "IO_L16N_T2_A27_15_F13") (pintype "bidirectional"))
    )
    (net (code "29") (name "/ADD12") (class "Default")
      (node (ref "U4") (pin "D11") (pinfunction "IO_L14N_T2_SRCC_15_D11") (pintype "bidirectional"))
    )
    (net (code "30") (name "/ADD13") (class "Default")
      (node (ref "U4") (pin "G11") (pinfunction "IO_25_15_G11") (pintype "bidirectional"))
    )
    (net (code "31") (name "/ADD14") (class "Default")
      (node (ref "U4") (pin "H13") (pinfunction "IO_L20N_T3_A19_15_H13") (pintype "bidirectional"))
    )
    (net (code "33") (name "/B1") (class "Default")
      (node (ref "U4") (pin "D3") (pinfunction "IO_L11N_T1_SRCC_35_D3") (pintype "bidirectional"))
    )
    (net (code "34") (name "/B2") (class "Default")
      (node (ref "U4") (pin "A4") (pinfunction "IO_L3N_T0_DQS_AD5N_35_A4") (pintype "bidirectional"))
    )
    (net (code "35") (name "/B4") (class "Default")
      (node (ref "U4") (pin "D5") (pinfunction "IO_L6N_T0_VREF_35_D5") (pintype "bidirectional"))
    )
    (net (code "36") (name "/B5") (class "Default")
      (node (ref "U4") (pin "F4") (pinfunction "IO_L14P_T2_SRCC_35_F4") (pintype "bidirectional"))
    )
    (net (code "37") (name "/B6") (class "Default")
      (node (ref "U4") (pin "F5") (pinfunction "IO_L13P_T2_MRCC_35_F5") (pintype "bidirectional"))
    )
    (net (code "38") (name "/B7") (class "Default")
      (node (ref "U4") (pin "D4") (pinfunction "IO_L12P_T1_MRCC_35_D4") (pintype "bidirectional"))
    )
    (net (code "39") (name "/BA0") (class "Default")
      (node (ref "U4") (pin "C8") (pinfunction "IO_L1P_T0_AD0P_15_C8") (pintype "bidirectional"))
    )
    (net (code "40") (name "/BA1") (class "Default")
      (node (ref "U4") (pin "C12") (pinfunction "IO_L11N_T1_SRCC_15_C12") (pintype "bidirectional"))
    )
    (net (code "41") (name "/BA2") (class "Default")
      (node (ref "U4") (pin "D9") (pinfunction "IO_L6N_T0_VREF_15_D9") (pintype "bidirectional"))
    )
    (net (code "43") (name "/C1") (class "Default")
      (node (ref "U4") (pin "B4") (pinfunction "IO_L4P_T0_35_B4") (pintype "bidirectional"))
    )
    (net (code "44") (name "/C2") (class "Default")
      (node (ref "U4") (pin "C4") (pinfunction "IO_L12N_T1_MRCC_35_C4") (pintype "bidirectional"))
    )
    (net (code "45") (name "/C3") (class "Default")
      (node (ref "U4") (pin "B5") (pinfunction "IO_L2N_T0_AD12N_35_B5") (pintype "bidirectional"))
    )
    (net (code "46") (name "/C4") (class "Default")
      (node (ref "U4") (pin "E1") (pinfunction "IO_L15N_T2_DQS_35_E1") (pintype "bidirectional"))
    )
    (net (code "47") (name "/C6") (class "Default")
      (node (ref "U4") (pin "E5") (pinfunction "IO_L13N_T2_MRCC_35_E5") (pintype "bidirectional"))
    )
    (net (code "48") (name "/C7") (class "Default")
      (node (ref "U4") (pin "B6") (pinfunction "IO_L2P_T0_AD12P_35_B6") (pintype "bidirectional"))
    )
    (net (code "49") (name "/CKE") (class "Default")
      (node (ref "U4") (pin "G12") (pinfunction "IO_L19N_T3_A21_VREF_15_G12") (pintype "bidirectional"))
    )
    (net (code "50") (name "/CK_N") (class "Default")
      (node (ref "U4") (pin "H16") (pinfunction "IO_L22P_T3_A17_15_H16") (pintype "bidirectional"))
    )
    (net (code "51") (name "/CK_P") (class "Default")
      (node (ref "U4") (pin "G16") (pinfunction "IO_L22N_T3_A16_15_G16") (pintype "bidirectional"))
    )
    (net (code "52") (name "/CONFIG_TCK") (class "Default")
      (node (ref "U4") (pin "L7") (pinfunction "TCK_0_L7") (pintype "input"))
    )
    (net (code "53") (name "/CONFIG_TDI") (class "Default")
      (node (ref "U4") (pin "N7") (pinfunction "TDI_0_N7") (pintype "input"))
    )
    (net (code "54") (name "/CONFIG_TDO") (class "Default")
      (node (ref "U4") (pin "N8") (pinfunction "TDO_0_N8") (pintype "output"))
    )
    (net (code "55") (name "/CONFIG_TMS") (class "Default")
      (node (ref "U4") (pin "M7") (pinfunction "TMS_0_M7") (pintype "input"))
    )
    (net (code "56") (name "/D1") (class "Default")
      (node (ref "U4") (pin "B1") (pinfunction "IO_L9N_T1_DQS_AD7N_35_B1") (pintype "bidirectional"))
    )
    (net (code "57") (name "/D3") (class "Default")
      (node (ref "U4") (pin "A2") (pinfunction "IO_L8N_T1_AD14N_35_A2") (pintype "bidirectional"))
    )
    (net (code "58") (name "/D4") (class "Default")
      (node (ref "U4") (pin "E2") (pinfunction "IO_L10P_T1_AD15P_35_E2") (pintype "bidirectional"))
    )
    (net (code "59") (name "/D5") (class "Default")
      (node (ref "U4") (pin "A5") (pinfunction "IO_L3P_T0_DQS_AD5P_35_A5") (pintype "bidirectional"))
    )
    (net (code "60") (name "/D6") (class "Default")
      (node (ref "U4") (pin "A7") (pinfunction "IO_L1N_T0_AD4N_35_A7") (pintype "bidirectional"))
    )
    (net (code "61") (name "/DONE") (class "Default")
      (node (ref "R16") (pin "1") (pinfunction "1_1") (pintype "passive"))
      (node (ref "R17") (pin "1") (pinfunction "1_1") (pintype "passive"))
      (node (ref "U4") (pin "H10") (pinfunction "DONE_0_H10") (pintype "bidirectional"))
    )
    (net (code "62") (name "/DQ0") (class "Default")
      (node (ref "U4") (pin "C14") (pinfunction "IO_L8P_T1_AD10P_15_C14") (pintype "bidirectional"))
    )
    (net (code "63") (name "/DQ1") (class "Default")
      (node (ref "U4") (pin "B12") (pinfunction "IO_L5P_T0_AD9P_15_B12") (pintype "bidirectional"))
    )
    (net (code "64") (name "/DQ2") (class "Default")
      (node (ref "U4") (pin "D15") (pinfunction "IO_L15N_T2_DQS_ADV_B_15_D15") (pintype "bidirectional"))
    )
    (net (code "65") (name "/DQ3") (class "Default")
      (node (ref "U4") (pin "A15") (pinfunction "IO_L9N_T1_DQS_AD3N_15_A15") (pintype "bidirectional"))
    )
    (net (code "66") (name "/DQ4") (class "Default")
      (node (ref "U4") (pin "E15") (pinfunction "IO_L18N_T2_A23_15_E15") (pintype "bidirectional"))
    )
    (net (code "67") (name "/DQ5") (class "Default")
      (node (ref "U4") (pin "C13") (pinfunction "IO_L12N_T1_MRCC_15_C13") (pintype "bidirectional"))
    )
    (net (code "68") (name "/DQ6") (class "Default")
      (node (ref "U4") (pin "D14") (pinfunction "IO_L15P_T2_DQS_15_D14") (pintype "bidirectional"))
    )
    (net (code "69") (name "/DQ7") (class "Default")
      (node (ref "U4") (pin "F15") (pinfunction "IO_L18P_T2_A24_15_F15") (pintype "bidirectional"))
    )
    (net (code "70") (name "/DQ8") (class "Default")
      (node (ref "U4") (pin "A10") (pinfunction "IO_L3N_T0_DQS_AD1N_15_A10") (pintype "bidirectional"))
    )
    (net (code "71") (name "/DQ9") (class "Default")
      (node (ref "U4") (pin "A14") (pinfunction "IO_L7N_T1_AD2N_15_A14") (pintype "bidirectional"))
    )
    (net (code "72") (name "/DQ10") (class "Default")
      (node (ref "U4") (pin "B9") (pinfunction "IO_L3P_T0_DQS_AD1P_15_B9") (pintype "bidirectional"))
    )
    (net (code "73") (name "/DQ11") (class "Default")
      (node (ref "U4") (pin "A13") (pinfunction "IO_L7P_T1_AD2P_15_A13") (pintype "bidirectional"))
    )
    (net (code "74") (name "/DQ12") (class "Default")
      (node (ref "U4") (pin "A8") (pinfunction "IO_L2P_T0_AD8P_15_A8") (pintype "bidirectional"))
    )
    (net (code "75") (name "/DQ13") (class "Default")
      (node (ref "U4") (pin "A12") (pinfunction "IO_L5N_T0_AD9N_15_A12") (pintype "bidirectional"))
    )
    (net (code "76") (name "/DQ14") (class "Default")
      (node (ref "U4") (pin "A9") (pinfunction "IO_L2N_T0_AD8N_15_A9") (pintype "bidirectional"))
    )
    (net (code "77") (name "/DQ15") (class "Default")
      (node (ref "U4") (pin "B10") (pinfunction "IO_L4P_T0_15_B10") (pintype "bidirectional"))
    )
    (net (code "79") (name "/E1") (class "Default")
      (node (ref "U4") (pin "D1") (pinfunction "IO_L10N_T1_AD15N_35_D1") (pintype "bidirectional"))
    )
    (net (code "80") (name "/E2") (class "Default")
      (node (ref "U4") (pin "B2") (pinfunction "IO_L8P_T1_AD14P_35_B2") (pintype "bidirectional"))
    )
    (net (code "81") (name "/E3") (class "Default")
      (node (ref "U4") (pin "C3") (pinfunction "IO_L7P_T1_AD6P_35_C3") (pintype "bidirectional"))
    )
    (net (code "82") (name "/E5") (class "Default")
      (node (ref "U4") (pin "C2") (pinfunction "IO_L7N_T1_AD6N_35_C2") (pintype "bidirectional"))
    )
    (net (code "83") (name "/E6") (class "Default")
      (node (ref "U4") (pin "H5") (pinfunction "IO_L18P_T2_35_H5") (pintype "bidirectional"))
    )
    (net (code "84") (name "/F2") (class "Default")
      (node (ref "U4") (pin "C1") (pinfunction "IO_L9P_T1_DQS_AD7P_35_C1") (pintype "bidirectional"))
    )
    (net (code "85") (name "/F3") (class "Default")
      (node (ref "U4") (pin "F2") (pinfunction "IO_L15P_T2_DQS_35_F2") (pintype "bidirectional"))
    )
    (net (code "86") (name "/F4") (class "Default")
      (node (ref "U4") (pin "F3") (pinfunction "IO_L14N_T2_SRCC_35_F3") (pintype "bidirectional"))
    )
    (net (code "87") (name "/F5") (class "Default")
      (node (ref "U4") (pin "E3") (pinfunction "IO_L11P_T1_SRCC_35_E3") (pintype "bidirectional"))
    )
    (net (code "88") (name "/G1") (class "Default")
      (node (ref "U4") (pin "H3") (pinfunction "IO_L21N_T3_DQS_35_H3") (pintype "bidirectional"))
    )
    (net (code "89") (name "/G2") (class "Default")
      (node (ref "U4") (pin "H2") (pinfunction "IO_L20P_T3_35_H2") (pintype "bidirectional"))
    )
    (net (code "90") (name "/G4") (class "Default")
      (node (ref "U4") (pin "G1") (pinfunction "IO_L17N_T2_35_G1") (pintype "bidirectional"))
    )
    (net (code "91") (name "/G5") (class "Default")
      (node (ref "U4") (pin "H4") (pinfunction "IO_L18N_T2_35_H4") (pintype "bidirectional"))
    )
    (net (code "92") (name "/H1") (class "Default")
      (node (ref "U4") (pin "J4") (pinfunction "IO_L19N_T3_VREF_35_J4") (pintype "bidirectional"))
    )
    (net (code "93") (name "/H2") (class "Default")
      (node (ref "U4") (pin "J3") (pinfunction "IO_L21P_T3_DQS_35_J3") (pintype "bidirectional"))
    )
    (net (code "94") (name "/H3") (class "Default")
      (node (ref "U4") (pin "L2") (pinfunction "IO_L23N_T3_35_L2") (pintype "bidirectional"))
    )
    (net (code "95") (name "/H4") (class "Default")
      (node (ref "U4") (pin "L3") (pinfunction "IO_L23P_T3_35_L3") (pintype "bidirectional"))
    )
    (net (code "96") (name "/H5") (class "Default")
      (node (ref "U4") (pin "K3") (pinfunction "IO_L24P_T3_35_K3") (pintype "bidirectional"))
    )
    (net (code "97") (name "/IN_Filter_ADC_N") (class "Default")
      (node (ref "R21") (pin "2") (pinfunction "2_2") (pintype "passive"))
    )
    (net (code "98") (name "/IN_Filter_ADC_P") (class "Default")
      (node (ref "R20") (pin "2") (pinfunction "2_2") (pintype "passive"))
    )
    (net (code "99") (name "/J1") (class "Default")
      (node (ref "U4") (pin "J5") (pinfunction "IO_L19P_T3_35_J5") (pintype "bidirectional"))
    )
    (net (code "100") (name "/J3") (class "Default")
      (node (ref "U4") (pin "K2") (pinfunction "IO_L24N_T3_35_K2") (pintype "bidirectional"))
    )
    (net (code "101") (name "/J4") (class "Default")
      (node (ref "U4") (pin "J1") (pinfunction "IO_L22N_T3_35_J1") (pintype "bidirectional"))
    )
    (net (code "102") (name "/J5") (class "Default")
      (node (ref "U4") (pin "H1") (pinfunction "IO_L20N_T3_35_H1") (pintype "bidirectional"))
    )
    (net (code "103") (name "/K1") (class "Default")
      (node (ref "U4") (pin "K5") (pinfunction "IO_25_35_K5") (pintype "bidirectional"))
    )
    (net (code "104") (name "/K2") (class "Default")
      (node (ref "U4") (pin "G4") (pinfunction "IO_L16N_T2_35_G4") (pintype "bidirectional"))
    )
    (net (code "105") (name "/K3") (class "Default")
      (node (ref "U4") (pin "G5") (pinfunction "IO_L16P_T2_35_G5") (pintype "bidirectional"))
    )
    (net (code "106") (name "/K5") (class "Default")
      (node (ref "U4") (pin "E6") (pinfunction "IO_0_35_E6") (pintype "bidirectional"))
    )
    (net (code "107") (name "/K13") (class "Default")
      (node (ref "U4") (pin "N6") (pinfunction "IO_L19N_T3_A09_D25_VREF_14_N6") (pintype "bidirectional"))
    )
    (net (code "108") (name "/L1_N") (class "Default")
      (node (ref "U4") (pin "P1") (pinfunction "IO_L4N_T0_34_P1") (pintype "bidirectional"))
    )
    (net (code "109") (name "/L1_P") (class "Default")
      (node (ref "U4") (pin "N1") (pinfunction "IO_L4P_T0_34_N1") (pintype "bidirectional"))
    )
    (net (code "110") (name "/L2") (class "Default")
      (node (ref "U4") (pin "G2") (pinfunction "IO_L17P_T2_35_G2") (pintype "bidirectional"))
    )
    (net (code "111") (name "/L2_N") (class "Default")
      (node (ref "U4") (pin "M4") (pinfunction "IO_L1N_T0_34_M4") (pintype "bidirectional"))
    )
    (net (code "112") (name "/L2_P") (class "Default")
      (node (ref "U4") (pin "L4") (pinfunction "IO_L1P_T0_34_L4") (pintype "bidirectional"))
    )
    (net (code "113") (name "/L3") (class "Default")
      (node (ref "U4") (pin "K1") (pinfunction "IO_L22P_T3_35_K1") (pintype "bidirectional"))
    )
    (net (code "114") (name "/L3_N") (class "Default")
      (node (ref "U4") (pin "R1") (pinfunction "IO_L7N_T1_34_R1") (pintype "bidirectional"))
    )
    (net (code "115") (name "/L3_P") (class "Default")
      (node (ref "U4") (pin "R2") (pinfunction "IO_L7P_T1_34_R2") (pintype "bidirectional"))
    )
    (net (code "116") (name "/L4_N") (class "Default")
      (node (ref "U4") (pin "M1") (pinfunction "IO_L2N_T0_34_M1") (pintype "bidirectional"))
    )
    (net (code "117") (name "/L4_P") (class "Default")
      (node (ref "U4") (pin "M2") (pinfunction "IO_L2P_T0_34_M2") (pintype "bidirectional"))
    )
    (net (code "118") (name "/L5") (class "Default")
      (node (ref "U4") (pin "L5") (pinfunction "IO_0_34_L5") (pintype "bidirectional"))
    )
    (net (code "119") (name "/L5_N") (class "Default")
      (node (ref "U4") (pin "T2") (pinfunction "IO_L8N_T1_34_T2") (pintype "bidirectional"))
    )
    (net (code "120") (name "/L5_P") (class "Default")
      (node (ref "U4") (pin "R3") (pinfunction "IO_L8P_T1_34_R3") (pintype "bidirectional"))
    )
    (net (code "121") (name "/L6_N") (class "Default")
      (node (ref "U4") (pin "N2") (pinfunction "IO_L3N_T0_DQS_34_N2") (pintype "bidirectional"))
    )
    (net (code "122") (name "/L6_P") (class "Default")
      (node (ref "U4") (pin "N3") (pinfunction "IO_L3P_T0_DQS_34_N3") (pintype "bidirectional"))
    )
    (net (code "123") (name "/L7_N") (class "Default")
      (node (ref "U4") (pin "T3") (pinfunction "IO_L9N_T1_DQS_34_T3") (pintype "bidirectional"))
    )
    (net (code "124") (name "/L7_P") (class "Default")
      (node (ref "U4") (pin "T4") (pinfunction "IO_L9P_T1_DQS_34_T4") (pintype "bidirectional"))
    )
    (net (code "125") (name "/L8_N") (class "Default")
      (node (ref "U4") (pin "P3") (pinfunction "IO_L5N_T0_34_P3") (pintype "bidirectional"))
    )
    (net (code "126") (name "/L8_P") (class "Default")
      (node (ref "U4") (pin "P4") (pinfunction "IO_L5P_T0_34_P4") (pintype "bidirectional"))
    )
    (net (code "127") (name "/L9_N") (class "Default")
      (node (ref "U4") (pin "N4") (pinfunction "IO_L6N_T0_VREF_34_N4") (pintype "bidirectional"))
    )
    (net (code "128") (name "/L9_P") (class "Default")
      (node (ref "U4") (pin "M5") (pinfunction "IO_L6P_T0_34_M5") (pintype "bidirectional"))
    )
    (net (code "129") (name "/L13") (class "Default")
      (node (ref "U4") (pin "M14") (pinfunction "IO_L4N_T0_D05_14_M14") (pintype "bidirectional"))
    )
    (net (code "130") (name "/LDM") (class "Default")
      (node (ref "U4") (pin "B14") (pinfunction "IO_L8N_T1_AD10N_15_B14") (pintype "bidirectional"))
    )
    (net (code "131") (name "/LDQS_N") (class "Default")
      (node (ref "U4") (pin "E16") (pinfunction "IO_L17P_T2_A26_15_E16") (pintype "bidirectional"))
    )
    (net (code "132") (name "/LDQS_P") (class "Default")
      (node (ref "U4") (pin "D16") (pinfunction "IO_L17N_T2_A25_15_D16") (pintype "bidirectional"))
    )
    (net (code "133") (name "/LED0") (class "Default")
      (node (ref "U4") (pin "T15") (pinfunction "IO_L10N_T1_D15_14_T15") (pintype "bidirectional"))
    )
    (net (code "134") (name "/LED1") (class "Default")
      (node (ref "U4") (pin "R15") (pinfunction "IO_L9P_T1_DQS_14_R15") (pintype "bidirectional"))
    )
    (net (code "135") (name "/LED2") (class "Default")
      (node (ref "U4") (pin "R16") (pinfunction "IO_L9N_T1_DQS_D13_14_R16") (pintype "bidirectional"))
    )
    (net (code "136") (name "/LED3") (class "Default")
      (node (ref "U4") (pin "P15") (pinfunction "IO_L8P_T1_D11_14_P15") (pintype "bidirectional"))
    )
    (net (code "137") (name "/LED4") (class "Default")
      (node (ref "U4") (pin "P16") (pinfunction "IO_L8N_T1_D12_14_P16") (pintype "bidirectional"))
    )
    (net (code "138") (name "/LED5") (class "Default")
      (node (ref "U4") (pin "N16") (pinfunction "IO_L7N_T1_D10_14_N16") (pintype "bidirectional"))
    )
    (net (code "139") (name "/LED6") (class "Default")
      (node (ref "U4") (pin "M15") (pinfunction "IO_L3N_T0_DQS_EMCCLK_14_M15") (pintype "bidirectional"))
    )
    (net (code "140") (name "/LED7") (class "Default")
      (node (ref "U4") (pin "M16") (pinfunction "IO_L7P_T1_D09_14_M16") (pintype "bidirectional"))
    )
    (net (code "141") (name "/M6") (class "Default")
      (node (ref "U4") (pin "L14") (pinfunction "IO_L4P_T0_D04_14_L14") (pintype "bidirectional"))
    )
    (net (code "142") (name "/M15") (class "Default")
      (node (ref "U4") (pin "P8") (pinfunction "IO_L20P_T3_A08_D24_14_P8") (pintype "bidirectional"))
    )
    (net (code "143") (name "/N6") (class "Default")
      (node (ref "U4") (pin "M12") (pinfunction "IO_L6N_T0_D08_VREF_14_M12") (pintype "bidirectional"))
    )
    (net (code "144") (name "/N9") (class "Default")
      (node (ref "U4") (pin "T9") (pinfunction "IO_L22P_T3_A05_D21_14_T9") (pintype "bidirectional"))
    )
    (net (code "145") (name "/N11") (class "Default")
      (node (ref "U4") (pin "P11") (pinfunction "IO_L14N_T2_SRCC_14_P11") (pintype "bidirectional"))
    )
    (net (code "146") (name "/N12") (class "Default")
      (node (ref "U4") (pin "N12") (pinfunction "IO_L13N_T2_MRCC_14_N12") (pintype "bidirectional"))
    )
    (net (code "147") (name "/N13") (class "Default")
      (node (ref "U4") (pin "P9") (pinfunction "IO_L18N_T2_A11_D27_14_P9") (pintype "bidirectional"))
    )
    (net (code "148") (name "/ODT") (class "Default")
      (node (ref "U4") (pin "G15") (pinfunction "IO_L24N_T3_RS0_15_G15") (pintype "bidirectional"))
    )
    (net (code "149") (name "/P5") (class "Default")
      (node (ref "U4") (pin "P5") (pinfunction "IO_L10P_T1_34_P5") (pintype "bidirectional"))
    )
    (net (code "150") (name "/P8") (class "Default")
      (node (ref "U4") (pin "T8") (pinfunction "IO_L21N_T3_DQS_A06_D22_14_T8") (pintype "bidirectional"))
    )
    (net (code "151") (name "/P9") (class "Default")
      (node (ref "U4") (pin "R8") (pinfunction "IO_L20N_T3_A07_D23_14_R8") (pintype "bidirectional"))
    )
    (net (code "152") (name "/P10") (class "Default")
      (node (ref "U4") (pin "R10") (pinfunction "IO_L17P_T2_A14_D30_14_R10") (pintype "bidirectional"))
    )
    (net (code "153") (name "/P11") (class "Default")
      (node (ref "U4") (pin "T12") (pinfunction "IO_L15N_T2_DQS_DOUT_CSO_B_14_T12") (pintype "bidirectional"))
    )
    (net (code "154") (name "/P13") (class "Default")
      (node (ref "U4") (pin "N9") (pinfunction "IO_L18P_T2_A12_D28_14_N9") (pintype "bidirectional"))
    )
    (net (code "155") (name "/P14") (class "Default")
      (node (ref "U4") (pin "T10") (pinfunction "IO_L22N_T3_A04_D20_14_T10") (pintype "bidirectional"))
    )
    (net (code "156") (name "/PROGRAM_B") (class "Default")
      (node (ref "R19") (pin "1") (pinfunction "1_1") (pintype "passive"))
      (node (ref "U4") (pin "L9") (pinfunction "PROGRAM_B_0_L9") (pintype "input"))
    )
    (net (code "157") (name "/QSPI_CLK") (class "Default")
      (node (ref "U4") (pin "E8") (pinfunction "CCLK_0_E8") (pintype "bidirectional"))
    )
    (net (code "158") (name "/QSPI_DATA0") (class "Default")
      (node (ref "U4") (pin "K16") (pinfunction "IO_L2N_T0_D03_14_K16") (pintype "bidirectional"))
    )
    (net (code "159") (name "/QSPI_DATA1") (class "Default")
      (node (ref "U4") (pin "J14") (pinfunction "IO_L1N_T0_D01_DIN_14_J14") (pintype "bidirectional"))
    )
    (net (code "160") (name "/QSPI_DATA2") (class "Default")
      (node (ref "U4") (pin "K15") (pinfunction "IO_L2P_T0_D02_14_K15") (pintype "bidirectional"))
    )
    (net (code "161") (name "/QSPI_DATA3") (class "Default")
      (node (ref "U4") (pin "J13") (pinfunction "IO_L1P_T0_D00_MOSI_14_J13") (pintype "bidirectional"))
    )
    (net (code "162") (name "/QSPI_~{CS}") (class "Default")
      (node (ref "U4") (pin "L12") (pinfunction "IO_L6P_T0_FCS_B_14_L12") (pintype "bidirectional"))
    )
    (net (code "163") (name "/R7") (class "Default")
      (node (ref "U4") (pin "T5") (pinfunction "IO_L23N_T3_A02_D18_14_T5") (pintype "bidirectional"))
    )
    (net (code "164") (name "/R8") (class "Default")
      (node (ref "U4") (pin "T7") (pinfunction "IO_L21P_T3_DQS_14_T7") (pintype "bidirectional"))
    )
    (net (code "165") (name "/R10") (class "Default")
      (node (ref "U4") (pin "N13") (pinfunction "IO_L11P_T1_SRCC_14_N13") (pintype "bidirectional"))
    )
    (net (code "166") (name "/R11") (class "Default")
      (node (ref "U4") (pin "N14") (pinfunction "IO_L12P_T1_MRCC_14_N14") (pintype "bidirectional"))
    )
    (net (code "167") (name "/R12") (class "Default")
      (node (ref "U4") (pin "P14") (pinfunction "IO_L12N_T1_MRCC_14_P14") (pintype "bidirectional"))
    )
    (net (code "168") (name "/R13") (class "Default")
      (node (ref "U4") (pin "R11") (pinfunction "IO_L17N_T2_A13_D29_14_R11") (pintype "bidirectional"))
    )
    (net (code "169") (name "/R15") (class "Default")
      (node (ref "U4") (pin "T13") (pinfunction "IO_L16N_T2_A15_D31_14_T13") (pintype "bidirectional"))
    )
    (net (code "170") (name "/R16") (class "Default")
      (node (ref "U4") (pin "R12") (pinfunction "IO_L15P_T2_DQS_RDWR_B_14_R12") (pintype "bidirectional"))
    )
    (net (code "171") (name "/RESET") (class "Default")
      (node (ref "U4") (pin "R5") (pinfunction "IO_L23P_T3_A03_D19_14_R5") (pintype "bidirectional"))
    )
    (net (code "172") (name "/T5") (class "Default")
      (node (ref "U4") (pin "K13") (pinfunction "IO_L5P_T0_D06_14_K13") (pintype "bidirectional"))
    )
    (net (code "173") (name "/T7") (class "Default")
      (node (ref "U4") (pin "K12") (pinfunction "IO_0_14_K12") (pintype "bidirectional"))
    )
    (net (code "174") (name "/T8") (class "Default")
      (node (ref "U4") (pin "L13") (pinfunction "IO_L5N_T0_D07_14_L13") (pintype "bidirectional"))
    )
    (net (code "175") (name "/T9") (class "Default")
      (node (ref "U4") (pin "R7") (pinfunction "IO_L24N_T3_A00_D16_14_R7") (pintype "bidirectional"))
    )
    (net (code "176") (name "/T10") (class "Default")
      (node (ref "U4") (pin "M6") (pinfunction "IO_L19P_T3_A10_D26_14_M6") (pintype "bidirectional"))
    )
    (net (code "177") (name "/T12") (class "Default")
      (node (ref "U4") (pin "P13") (pinfunction "IO_L11N_T1_SRCC_14_P13") (pintype "bidirectional"))
    )
    (net (code "178") (name "/T13") (class "Default")
      (node (ref "U4") (pin "P10") (pinfunction "IO_L14P_T2_SRCC_14_P10") (pintype "bidirectional"))
    )
    (net (code "179") (name "/T14") (class "Default")
      (node (ref "U4") (pin "T14") (pinfunction "IO_L10P_T1_D14_14_T14") (pintype "bidirectional"))
    )
    (net (code "180") (name "/T15") (class "Default")
      (node (ref "U4") (pin "R13") (pinfunction "IO_L16P_T2_CSI_B_14_R13") (pintype "bidirectional"))
    )
    (net (code "181") (name "/UART_RX") (class "Default")
      (node (ref "U4") (pin "P6") (pinfunction "IO_25_14_P6") (pintype "bidirectional"))
    )
    (net (code "182") (name "/UART_TX") (class "Default")
      (node (ref "U4") (pin "R6") (pinfunction "IO_L24P_T3_A01_D17_14_R6") (pintype "bidirectional"))
    )
    (net (code "183") (name "/UDM") (class "Default")
      (node (ref "U4") (pin "B15") (pinfunction "IO_L9P_T1_DQS_AD3P_15_B15") (pintype "bidirectional"))
    )
    (net (code "184") (name "/UDQS_N") (class "Default")
      (node (ref "U4") (pin "B16") (pinfunction "IO_L10N_T1_AD11N_15_B16") (pintype "bidirectional"))
    )
    (net (code "185") (name "/UDQS_P") (class "Default")
      (node (ref "U4") (pin "C16") (pinfunction "IO_L10P_T1_AD11P_15_C16") (pintype "bidirectional"))
    )
    (net (code "186") (name "/~{CAS}") (class "Default")
      (node (ref "U4") (pin "C11") (pinfunction "IO_L11P_T1_SRCC_15_C11") (pintype "bidirectional"))
    )
    (net (code "187") (name "/~{CS}") (class "Default")
      (node (ref "U4") (pin "J16") (pinfunction "IO_L23N_T3_FWE_B_15_J16") (pintype "bidirectional"))
    )
    (net (code "188") (name "/~{DDR_RESET}") (class "Default")
      (node (ref "U4") (pin "J15") (pinfunction "IO_L23P_T3_FOE_B_15_J15") (pintype "bidirectional"))
    )
    (net (code "189") (name "/~{RAS}") (class "Default")
      (node (ref "U4") (pin "C9") (pinfunction "IO_L1N_T0_AD0N_15_C9") (pintype "bidirectional"))
    )
    (net (code "190") (name "/~{WE}") (class "Default")
      (node (ref "U4") (pin "D10") (pinfunction "IO_0_15_D10") (pintype "bidirectional"))
    )
    (net (code "191") (name "AGND") (class "Default")
      (node (ref "C38") (pin "1") (pinfunction "1_1") (pintype "passive"))
      (node (ref "C51") (pin "1") (pinfunction "1_1") (pintype "passive"))
      (node (ref "C52") (pin "1") (pinfunction "1_1") (pintype "passive"))
      (node (ref "C53") (pin "1") (pinfunction "1_1") (pintype "passive"))
      (node (ref "L4") (pin "2") (pinfunction "2_2") (pintype "passive"))
      (node (ref "U4") (pin "G7") (pinfunction "GNDADC_0_G7") (pintype "power_in"))
      (node (ref "U4") (pin "H7") (pinfunction "VREFN_0_H7") (pintype "power_in"))
      (node (ref "U5") (pin "3") (pinfunction "GND_3") (pintype "passive"))
    )
    (net (code "192") (name "GND") (class "Default")
      (node (ref "C22") (pin "1") (pinfunction "1_1") (pintype "passive"))
      (node (ref "C23") (pin "1") (pinfunction "1_1") (pintype "passive"))
      (node (ref "C24") (pin "1") (pinfunction "1_1") (pintype "passive"))
      (node (ref "C25") (pin "1") (pinfunction "1_1") (pintype "passive"))
      (node (ref "C26") (pin "1") (pinfunction "1_1") (pintype "passive"))
      (node (ref "C27") (pin "1") (pinfunction "1_1") (pintype "passive"))
      (node (ref "C28") (pin "1") (pinfunction "1_1") (pintype "passive"))
      (node (ref "C29") (pin "1") (pinfunction "1_1") (pintype "passive"))
      (node (ref "C30") (pin "1") (pinfunction "1_1") (pintype "passive"))
      (node (ref "C31") (pin "1") (pinfunction "1_1") (pintype "passive"))
      (node (ref "C32") (pin "1") (pinfunction "1_1") (pintype "passive"))
      (node (ref "C33") (pin "1") (pinfunction "1_1") (pintype "passive"))
      (node (ref "C34") (pin "1") (pinfunction "1_1") (pintype "passive"))
      (node (ref "C35") (pin "1") (pinfunction "1_1") (pintype "passive"))
      (node (ref "C36") (pin "1") (pinfunction "1_1") (pintype "passive"))
      (node (ref "C37") (pin "1") (pinfunction "1_1") (pintype "passive"))
      (node (ref "C39") (pin "1") (pinfunction "1_1") (pintype "passive"))
      (node (ref "C40") (pin "1") (pinfunction "1_1") (pintype "passive"))
      (node (ref "C41") (pin "1") (pinfunction "1_1") (pintype "passive"))
      (node (ref "C42") (pin "1") (pinfunction "1_1") (pintype "passive"))
      (node (ref "C43") (pin "1") (pinfunction "1_1") (pintype "passive"))
      (node (ref "C44") (pin "1") (pinfunction "1_1") (pintype "passive"))
      (node (ref "C45") (pin "1") (pinfunction "1_1") (pintype "passive"))
      (node (ref "C46") (pin "1") (pinfunction "1_1") (pintype "passive"))
      (node (ref "C47") (pin "1") (pinfunction "1_1") (pintype "passive"))
      (node (ref "C48") (pin "1") (pinfunction "1_1") (pintype "passive"))
      (node (ref "C49") (pin "1") (pinfunction "1_1") (pintype "passive"))
      (node (ref "C50") (pin "1") (pinfunction "1_1") (pintype "passive"))
      (node (ref "C55") (pin "1") (pinfunction "1_1") (pintype "passive"))
      (node (ref "C56") (pin "1") (pinfunction "1_1") (pintype "passive"))
      (node (ref "C57") (pin "1") (pinfunction "1_1") (pintype "passive"))
      (node (ref "C58") (pin "1") (pinfunction "1_1") (pintype "passive"))
      (node (ref "C59") (pin "1") (pinfunction "1_1") (pintype "passive"))
      (node (ref "C60") (pin "1") (pinfunction "1_1") (pintype "passive"))
      (node (ref "C61") (pin "1") (pinfunction "1_1") (pintype "passive"))
      (node (ref "C62") (pin "1") (pinfunction "1_1") (pintype "passive"))
      (node (ref "C63") (pin "1") (pinfunction "1_1") (pintype "passive"))
      (node (ref "C64") (pin "1") (pinfunction "1_1") (pintype "passive"))
      (node (ref "C65") (pin "1") (pinfunction "1_1") (pintype "passive"))
      (node (ref "C66") (pin "1") (pinfunction "1_1") (pintype "passive"))
      (node (ref "C67") (pin "1") (pinfunction "1_1") (pintype "passive"))
      (node (ref "C68") (pin "1") (pinfunction "1_1") (pintype "passive"))
      (node (ref "D3") (pin "C") (pinfunction "C_C") (pintype "passive"))
      (node (ref "L4") (pin "1") (pinfunction "1_1") (pintype "passive"))
      (node (ref "U4") (pin "A1") (pinfunction "GND_A1") (pintype "power_in"))
      (node (ref "U4") (pin "A11") (pinfunction "GND_A11") (pintype "power_in"))
      (node (ref "U4") (pin "B8") (pinfunction "GND_B8") (pintype "power_in"))
      (node (ref "U4") (pin "C15") (pinfunction "GND_C15") (pintype "power_in"))
      (node (ref "U4") (pin "C5") (pinfunction "GND_C5") (pintype "power_in"))
      (node (ref "U4") (pin "D12") (pinfunction "GND_D12") (pintype "power_in"))
      (node (ref "U4") (pin "D2") (pinfunction "GND_D2") (pintype "power_in"))
      (node (ref "U4") (pin "E9") (pinfunction "GND_E9") (pintype "power_in"))
      (node (ref "U4") (pin "F10") (pinfunction "GND_F10") (pintype "power_in"))
      (node (ref "U4") (pin "F16") (pinfunction "GND_F16") (pintype "power_in"))
      (node (ref "U4") (pin "F6") (pinfunction "GND_F6") (pintype "power_in"))
      (node (ref "U4") (pin "F8") (pinfunction "VCCBATT_0_F8") (pintype "power_in"))
      (node (ref "U4") (pin "G13") (pinfunction "GND_G13") (pintype "power_in"))
      (node (ref "U4") (pin "G3") (pinfunction "GND_G3") (pintype "power_in"))
      (node (ref "U4") (pin "G9") (pinfunction "GND_G9") (pintype "power_in"))
      (node (ref "U4") (pin "H6") (pinfunction "GND_H6") (pintype "power_in"))
      (node (ref "U4") (pin "J11") (pinfunction "GND_J11") (pintype "power_in"))
      (node (ref "U4") (pin "J9") (pinfunction "GND_J9") (pintype "power_in"))
      (node (ref "U4") (pin "K14") (pinfunction "GND_K14") (pintype "power_in"))
      (node (ref "U4") (pin "K4") (pinfunction "GND_K4") (pintype "power_in"))
      (node (ref "U4") (pin "K6") (pinfunction "GND_K6") (pintype "power_in"))
      (node (ref "U4") (pin "K7") (pinfunction "DXN_0_K7") (pintype "input"))
      (node (ref "U4") (pin "K8") (pinfunction "DXP_0_K8") (pintype "input"))
      (node (ref "U4") (pin "L1") (pinfunction "GND_L1") (pintype "power_in"))
      (node (ref "U4") (pin "L11") (pinfunction "GND_L11") (pintype "power_in"))
      (node (ref "U4") (pin "M10") (pinfunction "M1_0_M10") (pintype "input"))
      (node (ref "U4") (pin "M11") (pinfunction "M2_0_M11") (pintype "input"))
      (node (ref "U4") (pin "M8") (pinfunction "GND_M8") (pintype "power_in"))
      (node (ref "U4") (pin "N15") (pinfunction "GND_N15") (pintype "power_in"))
      (node (ref "U4") (pin "N5") (pinfunction "GND_N5") (pintype "power_in"))
      (node (ref "U4") (pin "P12") (pinfunction "GND_P12") (pintype "power_in"))
      (node (ref "U4") (pin "P2") (pinfunction "GND_P2") (pintype "power_in"))
      (node (ref "U4") (pin "R9") (pinfunction "GND_R9") (pintype "power_in"))
      (node (ref "U4") (pin "T16") (pinfunction "GND_T16") (pintype "power_in"))
      (node (ref "U4") (pin "T6") (pinfunction "GND_T6") (pintype "power_in"))
      (node (ref "XTAL2") (pin "2") (pinfunction "GND_2") (pintype "power_in"))
    )
    (net (code "193") (name "Net-(D3-PadA)") (class "Default")
      (node (ref "D3") (pin "A") (pinfunction "A_A") (pintype "passive"))
      (node (ref "R17") (pin "2") (pinfunction "2_2") (pintype "passive"))
    )
    (net (code "194") (name "Net-(U4G-INIT_B_0)") (class "Default")
      (node (ref "R18") (pin "1") (pinfunction "1_1") (pintype "passive"))
      (node (ref "U4") (pin "K10") (pinfunction "INIT_B_0_K10") (pintype "bidirectional"))
    )
    (net (code "195") (name "unconnected-(U4C-IO_L19P_T3_A22_15-PadH11)") (class "Default")
      (node (ref "U4") (pin "H11") (pinfunction "IO_L19P_T3_A22_15_H11") (pintype "bidirectional+no_connect"))
    )
  )
)
